# Sheet3.net
KiCad netlist of a schematic drawn in Altium Designer
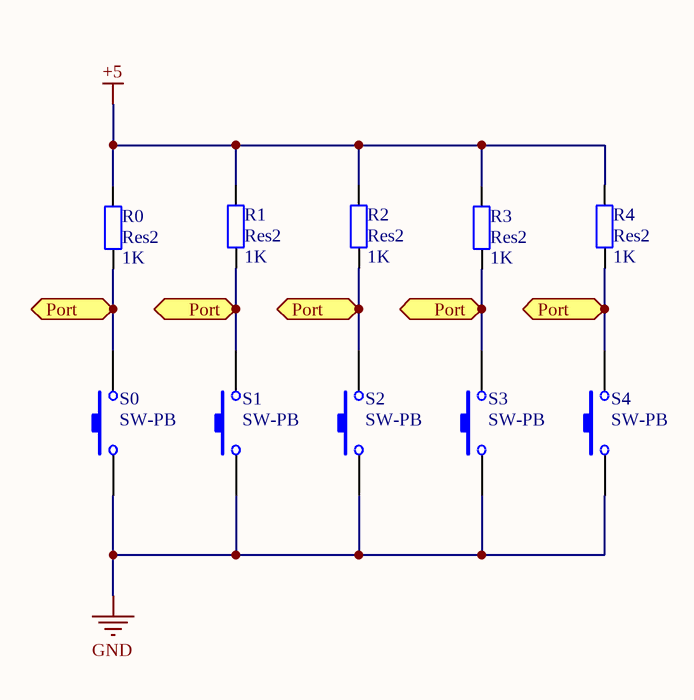
[diagram p0: Sheet3.SchDoc]

(export (version "E")
  (design (tool "Eeschema 10.0.6"))
  (components
    (comp (ref "R0")
      (value "Res2")
      (footprint "AXIAL-0.4")
      (description "Resistor")
      (fields (field (name "ALTIUM_VALUE") "1K") (field (name "PUBLISHER") "Altium Limited"))
      (libsource (lib "Miscellaneous Devices") (part "Res2"))
    )
    (comp (ref "R1")
      (value "Res2")
      (footprint "AXIAL-0.4")
      (description "Resistor")
      (fields (field (name "ALTIUM_VALUE") "1K") (field (name "PUBLISHER") "Altium Limited"))
      (libsource (lib "Miscellaneous Devices") (part "Res2"))
    )
    (comp (ref "R2")
      (value "Res2")
      (footprint "AXIAL-0.4")
      (description "Resistor")
      (fields (field (name "ALTIUM_VALUE") "1K") (field (name "PUBLISHER") "Altium Limited"))
      (libsource (lib "Miscellaneous Devices") (part "Res2"))
    )
    (comp (ref "R3")
      (value "Res2")
      (footprint "AXIAL-0.4")
      (description "Resistor")
      (fields (field (name "ALTIUM_VALUE") "1K") (field (name "PUBLISHER") "Altium Limited"))
      (libsource (lib "Miscellaneous Devices") (part "Res2"))
    )
    (comp (ref "R4")
      (value "Res2")
      (footprint "AXIAL-0.4")
      (description "Resistor")
      (fields (field (name "ALTIUM_VALUE") "1K") (field (name "PUBLISHER") "Altium Limited"))
      (libsource (lib "") (part "Res2_1"))
    )
    (comp (ref "S0")
      (value "SW-PB")
      (footprint "SPST-2")
      (description "Switch")
      (fields (field (name "PUBLISHER") "Altium Limited"))
      (libsource (lib "Miscellaneous Devices") (part "SW-PB"))
    )
    (comp (ref "S1")
      (value "SW-PB")
      (footprint "SPST-2")
      (description "Switch")
      (fields (field (name "PUBLISHER") "Altium Limited"))
      (libsource (lib "Miscellaneous Devices") (part "SW-PB"))
    )
    (comp (ref "S2")
      (value "SW-PB")
      (footprint "SPST-2")
      (description "Switch")
      (fields (field (name "PUBLISHER") "Altium Limited"))
      (libsource (lib "Miscellaneous Devices") (part "SW-PB"))
    )
    (comp (ref "S3")
      (value "SW-PB")
      (footprint "SPST-2")
      (description "Switch")
      (fields (field (name "PUBLISHER") "Altium Limited"))
      (libsource (lib "Miscellaneous Devices") (part "SW-PB"))
    )
    (comp (ref "S4")
      (value "SW-PB")
      (footprint "SPST-2")
      (description "Switch")
      (fields (field (name "PUBLISHER") "Altium Limited"))
      (libsource (lib "Miscellaneous Devices") (part "SW-PB"))
    )
  )
  (nets
    (net (code "1") (name "+5") (class "Default")
      (node (ref "R0") (pin "2") (pinfunction "2_2") (pintype "passive"))
      (node (ref "R1") (pin "2") (pinfunction "2_2") (pintype "passive"))
      (node (ref "R2") (pin "2") (pinfunction "2_2") (pintype "passive"))
      (node (ref "R3") (pin "2") (pinfunction "2_2") (pintype "passive"))
      (node (ref "R4") (pin "1") (pinfunction "1_1") (pintype "passive"))
    )
    (net (code "2") (name "/Port") (class "Default")
      (node (ref "R0") (pin "1") (pinfunction "1_1") (pintype "passive"))
      (node (ref "R1") (pin "1") (pinfunction "1_1") (pintype "passive"))
      (node (ref "R2") (pin "1") (pinfunction "1_1") (pintype "passive"))
      (node (ref "R3") (pin "1") (pinfunction "1_1") (pintype "passive"))
      (node (ref "R4") (pin "2") (pinfunction "2_2") (pintype "passive"))
      (node (ref "S0") (pin "2") (pinfunction "2_2") (pintype "passive"))
      (node (ref "S1") (pin "2") (pinfunction "2_2") (pintype "passive"))
      (node (ref "S2") (pin "2") (pinfunction "2_2") (pintype "passive"))
      (node (ref "S3") (pin "2") (pinfunction "2_2") (pintype "passive"))
      (node (ref "S4") (pin "2") (pinfunction "2_2") (pintype "passive"))
    )
    (net (code "3") (name "GND") (class "Default")
      (node (ref "S0") (pin "1") (pinfunction "1_1") (pintype "passive"))
      (node (ref "S1") (pin "1") (pinfunction "1_1") (pintype "passive"))
      (node (ref "S2") (pin "1") (pinfunction "1_1") (pintype "passive"))
      (node (ref "S3") (pin "1") (pinfunction "1_1") (pintype "passive"))
      (node (ref "S4") (pin "1") (pinfunction "1_1") (pintype "passive"))
    )
  )
)
